# FUFO.net
KiCad netlist of a schematic drawn in Altium Designer
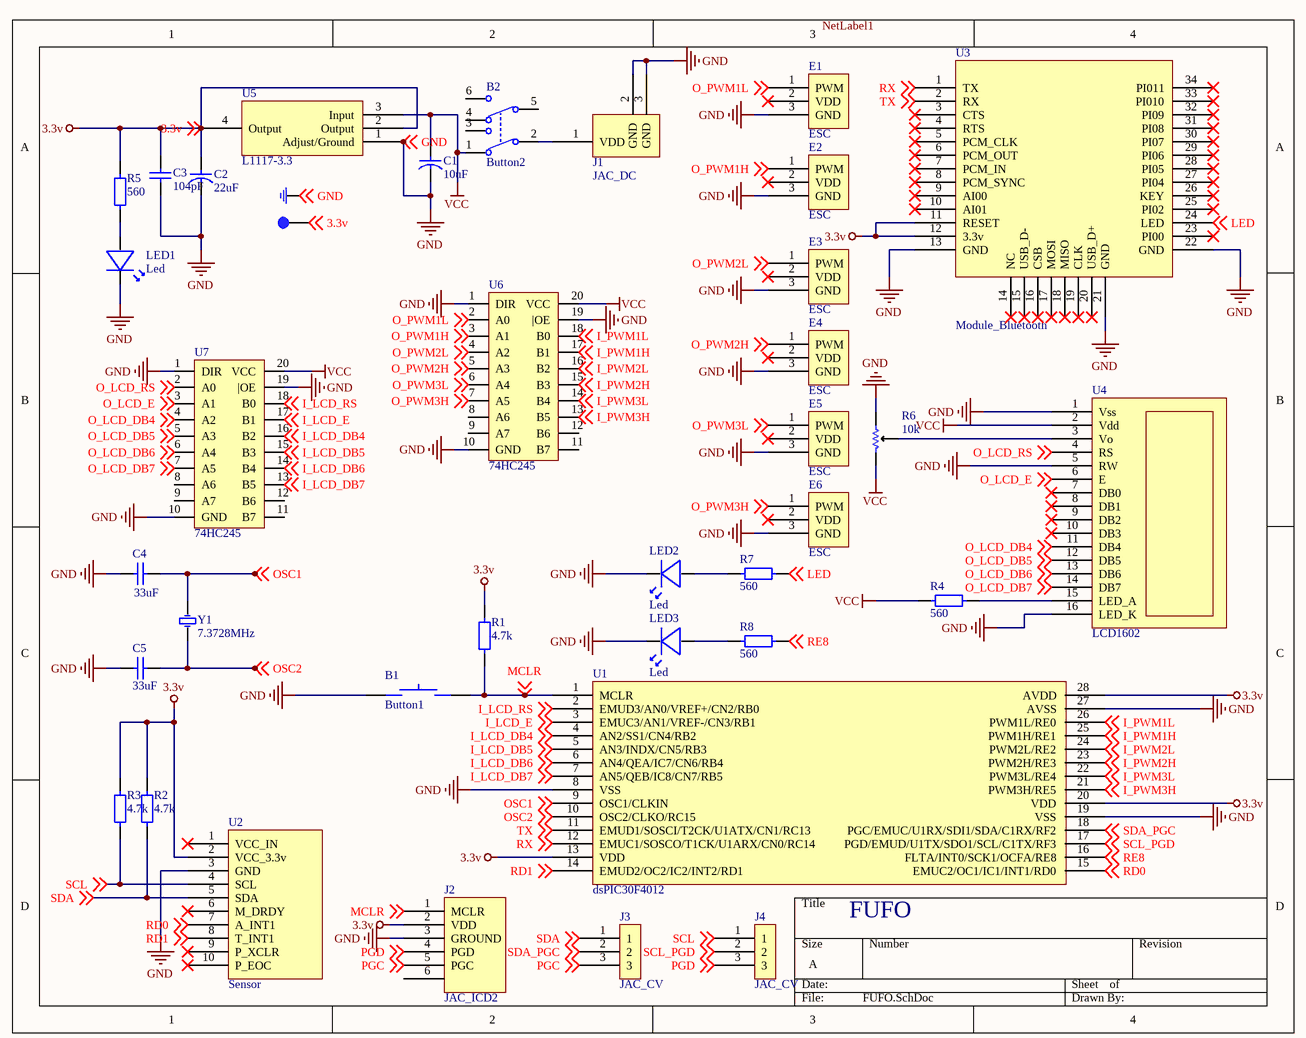
[diagram p0: FUFO.SchDoc]

(export (version "E")
  (design (tool "Eeschema 10.0.6"))
  (components
    (comp (ref "3.3v") (value "3.3v") (footprint "3.3v") (libsource (lib "FUFO") (part "3.3v")))
    (comp (ref "B1") (value "Button1") (footprint "Button1") (libsource (lib "FUFO") (part "Button1")))
    (comp (ref "B2") (value "Button2") (footprint "Button2") (libsource (lib "FUFO") (part "Button2")))
    (comp (ref "C1")
      (value "10uF")
      (footprint "Capacitor2")
      (description "Capacitor2")
      (libsource (lib "FUFO") (part "Capacitor2"))
    )
    (comp (ref "C2")
      (value "22uF")
      (footprint "Capacitor3")
      (description "Capacitor3")
      (libsource (lib "FUFO") (part "Capacitor3"))
    )
    (comp (ref "C3")
      (value "104pF")
      (footprint "Capacitor1")
      (description "Capacitor1")
      (libsource (lib "FUFO") (part "Capacitor1"))
    )
    (comp (ref "C4")
      (value "33uF")
      (footprint "Capacitor1")
      (description "Capacitor1")
      (libsource (lib "FUFO") (part "Capacitor1"))
    )
    (comp (ref "C5")
      (value "33uF")
      (footprint "Capacitor1")
      (description "Capacitor1")
      (libsource (lib "FUFO") (part "Capacitor1"))
    )
    (comp (ref "E1") (value "ESC") (footprint "ESC") (libsource (lib "FUFO") (part "ESC")))
    (comp (ref "E2") (value "ESC") (footprint "ESC") (libsource (lib "FUFO") (part "ESC")))
    (comp (ref "E3") (value "ESC") (footprint "ESC") (libsource (lib "FUFO") (part "ESC")))
    (comp (ref "E4") (value "ESC") (footprint "ESC") (libsource (lib "FUFO") (part "ESC")))
    (comp (ref "E5") (value "ESC") (footprint "ESC") (libsource (lib "FUFO") (part "ESC")))
    (comp (ref "E6") (value "ESC") (footprint "ESC") (libsource (lib "FUFO") (part "ESC")))
    (comp (ref "GND") (value "GND") (footprint "GND") (libsource (lib "FUFO") (part "GND")))
    (comp (ref "J1") (value "JAC_DC") (footprint "Jac_DC") (libsource (lib "FUFO") (part "JAC_DC")))
    (comp (ref "J2") (value "JAC_ICD2") (footprint "JAC_ICD2") (libsource (lib "FUFO") (part "JAC_ICD2")))
    (comp (ref "J3") (value "JAC_CV") (footprint "JAC_CV") (libsource (lib "FUFO") (part "JAC_CV")))
    (comp (ref "J4") (value "JAC_CV") (footprint "JAC_CV") (libsource (lib "FUFO") (part "JAC_CV")))
    (comp (ref "LED1") (value "Led") (footprint "LED") (libsource (lib "FUFO") (part "Led")))
    (comp (ref "LED2") (value "Led") (footprint "LED") (libsource (lib "FUFO") (part "Led")))
    (comp (ref "LED3") (value "Led") (footprint "LED") (libsource (lib "FUFO") (part "Led")))
    (comp (ref "R1") (value "4.7k") (footprint "Resistor") (libsource (lib "FUFO") (part "Resistor")))
    (comp (ref "R2") (value "4.7k") (footprint "Resistor") (libsource (lib "FUFO") (part "Resistor")))
    (comp (ref "R3") (value "4.7k") (footprint "Resistor") (libsource (lib "FUFO") (part "Resistor")))
    (comp (ref "R4") (value "560") (footprint "Resistor") (libsource (lib "FUFO") (part "Resistor")))
    (comp (ref "R5") (value "560") (footprint "Resistor") (libsource (lib "FUFO") (part "Resistor")))
    (comp (ref "R6") (value "10k") (footprint "BienTro") (libsource (lib "FUFO") (part "BienTro")))
    (comp (ref "R7") (value "560") (footprint "Resistor") (libsource (lib "FUFO") (part "Resistor")))
    (comp (ref "R8") (value "560") (footprint "Resistor") (libsource (lib "FUFO") (part "Resistor")))
    (comp (ref "U1")
      (value "dsPIC30F4012")
      (footprint "dsPIC30F4012")
      (libsource (lib "FUFO") (part "dsPIC30F4012"))
    )
    (comp (ref "U2") (value "Sensor") (footprint "Sensor") (libsource (lib "FUFO") (part "Sensor")))
    (comp (ref "U3")
      (value "Module_Bluetooth")
      (footprint "Module_Bluetooth")
      (libsource (lib "FUFO") (part "Module_Bluetooth"))
    )
    (comp (ref "U4") (value "LCD1602") (footprint "LCD1602") (libsource (lib "FUFO") (part "LCD1602")))
    (comp (ref "U5")
      (value "L1117-3.3")
      (footprint "L1117 - 3.3")
      (libsource (lib "FUFO") (part "L1117-3.3"))
    )
    (comp (ref "U6") (value "74HC245") (footprint "74HC245") (libsource (lib "FUFO") (part "74HC245")))
    (comp (ref "U7") (value "74HC245") (footprint "74HC245") (libsource (lib "FUFO") (part "74HC245")))
    (comp (ref "Y1") (value "7.3728MHz") (footprint "XTAL") (libsource (lib "FUFO") (part "XTAL")))
  )
  (nets
    (net (code "2") (name "3.3v") (class "Default")
      (node (ref "3.3v") (pin "0") (pinfunction "0_0") (pintype "passive"))
      (node (ref "C2") (pin "1") (pinfunction "1_1") (pintype "passive"))
      (node (ref "C3") (pin "2") (pinfunction "2_2") (pintype "passive"))
      (node (ref "J2") (pin "2") (pinfunction "VDD_2") (pintype "passive"))
      (node (ref "R1") (pin "2") (pinfunction "2_2") (pintype "passive"))
      (node (ref "R2") (pin "2") (pinfunction "2_2") (pintype "passive"))
      (node (ref "R3") (pin "2") (pinfunction "2_2") (pintype "passive"))
      (node (ref "R5") (pin "2") (pinfunction "2_2") (pintype "passive"))
      (node (ref "U1") (pin "13") (pinfunction "VDD_13") (pintype "passive"))
      (node (ref "U1") (pin "20") (pinfunction "VDD_20") (pintype "passive"))
      (node (ref "U1") (pin "28") (pinfunction "AVDD_28") (pintype "passive"))
      (node (ref "U2") (pin "2") (pinfunction "VCC_3.3v_2") (pintype "passive"))
      (node (ref "U3") (pin "11") (pinfunction "RESET_11") (pintype "passive"))
      (node (ref "U3") (pin "12") (pinfunction "3.3v_12") (pintype "passive"))
      (node (ref "U5") (pin "2") (pinfunction "Output_2") (pintype "passive"))
      (node (ref "U5") (pin "4") (pinfunction "Output_4") (pintype "passive"))
    )
    (net (code "3") (name "GND") (class "Default")
      (node (ref "B1") (pin "1") (pinfunction "1_1") (pintype "passive"))
      (node (ref "C1") (pin "2") (pinfunction "2_2") (pintype "passive"))
      (node (ref "C2") (pin "2") (pinfunction "2_2") (pintype "passive"))
      (node (ref "C3") (pin "1") (pinfunction "1_1") (pintype "passive"))
      (node (ref "C4") (pin "1") (pinfunction "1_1") (pintype "passive"))
      (node (ref "C5") (pin "1") (pinfunction "1_1") (pintype "passive"))
      (node (ref "E1") (pin "3") (pinfunction "GND_3") (pintype "passive"))
      (node (ref "E2") (pin "3") (pinfunction "GND_3") (pintype "passive"))
      (node (ref "E3") (pin "3") (pinfunction "GND_3") (pintype "passive"))
      (node (ref "E4") (pin "3") (pinfunction "GND_3") (pintype "passive"))
      (node (ref "E5") (pin "3") (pinfunction "GND_3") (pintype "passive"))
      (node (ref "E6") (pin "3") (pinfunction "GND_3") (pintype "passive"))
      (node (ref "GND") (pin "0") (pinfunction "0_0") (pintype "passive"))
      (node (ref "J1") (pin "2") (pinfunction "GND_2") (pintype "passive"))
      (node (ref "J1") (pin "3") (pinfunction "GND_3") (pintype "passive"))
      (node (ref "J2") (pin "3") (pinfunction "GROUND_3") (pintype "passive"))
      (node (ref "LED1") (pin "2") (pinfunction "2_2") (pintype "passive"))
      (node (ref "LED2") (pin "2") (pinfunction "2_2") (pintype "passive"))
      (node (ref "LED3") (pin "2") (pinfunction "2_2") (pintype "passive"))
      (node (ref "R6") (pin "0") (pinfunction "0_0") (pintype "passive"))
      (node (ref "U1") (pin "19") (pinfunction "VSS_19") (pintype "passive"))
      (node (ref "U1") (pin "27") (pinfunction "AVSS_27") (pintype "passive"))
      (node (ref "U1") (pin "8") (pinfunction "VSS_8") (pintype "passive"))
      (node (ref "U2") (pin "3") (pinfunction "GND_3") (pintype "passive"))
      (node (ref "U3") (pin "13") (pinfunction "GND_13") (pintype "passive"))
      (node (ref "U3") (pin "21") (pinfunction "GND_21") (pintype "passive"))
      (node (ref "U3") (pin "22") (pinfunction "GND_22") (pintype "passive"))
      (node (ref "U4") (pin "1") (pinfunction "Vss_1") (pintype "passive"))
      (node (ref "U4") (pin "16") (pinfunction "LED_K_16") (pintype "passive"))
      (node (ref "U4") (pin "5") (pinfunction "RW_5") (pintype "passive"))
      (node (ref "U5") (pin "1") (pinfunction "Adjust/Ground_1") (pintype "passive"))
      (node (ref "U6") (pin "1") (pinfunction "DIR_1") (pintype "passive"))
      (node (ref "U6") (pin "10") (pinfunction "GND_10") (pintype "passive"))
      (node (ref "U6") (pin "19") (pinfunction "OE_19") (pintype "passive"))
      (node (ref "U7") (pin "1") (pinfunction "DIR_1") (pintype "passive"))
      (node (ref "U7") (pin "10") (pinfunction "GND_10") (pintype "passive"))
      (node (ref "U7") (pin "19") (pinfunction "OE_19") (pintype "passive"))
    )
    (net (code "4") (name "I_LCD_DB4") (class "Default")
      (node (ref "U1") (pin "4") (pinfunction "AN2/SS1/CN4/RB2_4") (pintype "passive"))
      (node (ref "U7") (pin "16") (pinfunction "B2_16") (pintype "passive"))
    )
    (net (code "5") (name "I_LCD_DB5") (class "Default")
      (node (ref "U1") (pin "5") (pinfunction "AN3/INDX/CN5/RB3_5") (pintype "passive"))
      (node (ref "U7") (pin "15") (pinfunction "B3_15") (pintype "passive"))
    )
    (net (code "6") (name "I_LCD_DB6") (class "Default")
      (node (ref "U1") (pin "6") (pinfunction "AN4/QEA/IC7/CN6/RB4_6") (pintype "passive"))
      (node (ref "U7") (pin "14") (pinfunction "B4_14") (pintype "passive"))
    )
    (net (code "7") (name "I_LCD_DB7") (class "Default")
      (node (ref "U1") (pin "7") (pinfunction "AN5/QEB/IC8/CN7/RB5_7") (pintype "passive"))
      (node (ref "U7") (pin "13") (pinfunction "B5_13") (pintype "passive"))
    )
    (net (code "8") (name "I_LCD_E") (class "Default")
      (node (ref "U1") (pin "3") (pinfunction "EMUC3/AN1/VREF-/CN3/RB1_3") (pintype "passive"))
      (node (ref "U7") (pin "17") (pinfunction "B1_17") (pintype "passive"))
    )
    (net (code "9") (name "I_LCD_RS") (class "Default")
      (node (ref "U1") (pin "2") (pinfunction "EMUD3/AN0/VREF+/CN2/RB0_2") (pintype "passive"))
      (node (ref "U7") (pin "18") (pinfunction "B0_18") (pintype "passive"))
    )
    (net (code "10") (name "I_PWM1H") (class "Default")
      (node (ref "U1") (pin "25") (pinfunction "PWM1H/RE1_25") (pintype "passive"))
      (node (ref "U6") (pin "17") (pinfunction "B1_17") (pintype "passive"))
    )
    (net (code "11") (name "I_PWM1L") (class "Default")
      (node (ref "U1") (pin "26") (pinfunction "PWM1L/RE0_26") (pintype "passive"))
      (node (ref "U6") (pin "18") (pinfunction "B0_18") (pintype "passive"))
    )
    (net (code "12") (name "I_PWM2H") (class "Default")
      (node (ref "U1") (pin "23") (pinfunction "PWM2H/RE3_23") (pintype "passive"))
      (node (ref "U6") (pin "15") (pinfunction "B3_15") (pintype "passive"))
    )
    (net (code "13") (name "I_PWM2L") (class "Default")
      (node (ref "U1") (pin "24") (pinfunction "PWM2L/RE2_24") (pintype "passive"))
      (node (ref "U6") (pin "16") (pinfunction "B2_16") (pintype "passive"))
    )
    (net (code "14") (name "I_PWM3H") (class "Default")
      (node (ref "U1") (pin "21") (pinfunction "PWM3H/RE5_21") (pintype "passive"))
      (node (ref "U6") (pin "13") (pinfunction "B5_13") (pintype "passive"))
    )
    (net (code "15") (name "I_PWM3L") (class "Default")
      (node (ref "U1") (pin "22") (pinfunction "PWM3L/RE4_22") (pintype "passive"))
      (node (ref "U6") (pin "14") (pinfunction "B4_14") (pintype "passive"))
    )
    (net (code "16") (name "LED") (class "Default")
      (node (ref "R7") (pin "2") (pinfunction "2_2") (pintype "passive"))
      (node (ref "U3") (pin "24") (pinfunction "LED_24") (pintype "passive"))
    )
    (net (code "17") (name "MCLR") (class "Default")
      (node (ref "B1") (pin "2") (pinfunction "2_2") (pintype "passive"))
      (node (ref "J2") (pin "1") (pinfunction "MCLR_1") (pintype "passive"))
      (node (ref "R1") (pin "1") (pinfunction "1_1") (pintype "passive"))
      (node (ref "U1") (pin "1") (pinfunction "MCLR_1") (pintype "passive"))
    )
    (net (code "18") (name "Net-(B2-1)") (class "Default")
      (node (ref "B2") (pin "2") (pinfunction "1_2") (pintype "passive"))
      (node (ref "J1") (pin "1") (pinfunction "VDD_1") (pintype "passive"))
    )
    (net (code "19") (name "Net-(LED1-Pad1)") (class "Default")
      (node (ref "LED1") (pin "1") (pinfunction "1_1") (pintype "passive"))
      (node (ref "R5") (pin "1") (pinfunction "1_1") (pintype "passive"))
    )
    (net (code "20") (name "Net-(LED2-Pad1)") (class "Default")
      (node (ref "LED2") (pin "1") (pinfunction "1_1") (pintype "passive"))
      (node (ref "R7") (pin "1") (pinfunction "1_1") (pintype "passive"))
    )
    (net (code "21") (name "Net-(LED3-Pad1)") (class "Default")
      (node (ref "LED3") (pin "1") (pinfunction "1_1") (pintype "passive"))
      (node (ref "R8") (pin "1") (pinfunction "1_1") (pintype "passive"))
    )
    (net (code "22") (name "Net-(U4-LED_A)") (class "Default")
      (node (ref "R4") (pin "2") (pinfunction "2_2") (pintype "passive"))
      (node (ref "U4") (pin "15") (pinfunction "LED_A_15") (pintype "passive"))
    )
    (net (code "23") (name "Net-(U4-Vo)") (class "Default")
      (node (ref "R6") (pin "1") (pinfunction "1_1") (pintype "passive"))
      (node (ref "U4") (pin "3") (pinfunction "Vo_3") (pintype "passive"))
    )
    (net (code "24") (name "OSC1") (class "Default")
      (node (ref "C4") (pin "2") (pinfunction "2_2") (pintype "passive"))
      (node (ref "U1") (pin "9") (pinfunction "OSC1/CLKIN_9") (pintype "passive"))
      (node (ref "Y1") (pin "2") (pinfunction "2_2") (pintype "passive"))
    )
    (net (code "25") (name "OSC2") (class "Default")
      (node (ref "C5") (pin "2") (pinfunction "2_2") (pintype "passive"))
      (node (ref "U1") (pin "10") (pinfunction "OSC2/CLKO/RC15_10") (pintype "passive"))
      (node (ref "Y1") (pin "1") (pinfunction "1_1") (pintype "passive"))
    )
    (net (code "26") (name "O_LCD_DB4") (class "Default")
      (node (ref "U4") (pin "11") (pinfunction "DB4_11") (pintype "passive"))
      (node (ref "U7") (pin "4") (pinfunction "A2_4") (pintype "passive"))
    )
    (net (code "27") (name "O_LCD_DB5") (class "Default")
      (node (ref "U4") (pin "12") (pinfunction "DB5_12") (pintype "passive"))
      (node (ref "U7") (pin "5") (pinfunction "A3_5") (pintype "passive"))
    )
    (net (code "28") (name "O_LCD_DB6") (class "Default")
      (node (ref "U4") (pin "13") (pinfunction "DB6_13") (pintype "passive"))
      (node (ref "U7") (pin "6") (pinfunction "A4_6") (pintype "passive"))
    )
    (net (code "29") (name "O_LCD_DB7") (class "Default")
      (node (ref "U4") (pin "14") (pinfunction "DB7_14") (pintype "passive"))
      (node (ref "U7") (pin "7") (pinfunction "A5_7") (pintype "passive"))
    )
    (net (code "30") (name "O_LCD_E") (class "Default")
      (node (ref "U4") (pin "6") (pinfunction "E_6") (pintype "passive"))
      (node (ref "U7") (pin "3") (pinfunction "A1_3") (pintype "passive"))
    )
    (net (code "31") (name "O_LCD_RS") (class "Default")
      (node (ref "U4") (pin "4") (pinfunction "RS_4") (pintype "passive"))
      (node (ref "U7") (pin "2") (pinfunction "A0_2") (pintype "passive"))
    )
    (net (code "32") (name "O_PWM1H") (class "Default")
      (node (ref "E2") (pin "1") (pinfunction "PWM_1") (pintype "passive"))
      (node (ref "U6") (pin "3") (pinfunction "A1_3") (pintype "passive"))
    )
    (net (code "33") (name "O_PWM1L") (class "Default")
      (node (ref "E1") (pin "1") (pinfunction "PWM_1") (pintype "passive"))
      (node (ref "U6") (pin "2") (pinfunction "A0_2") (pintype "passive"))
    )
    (net (code "34") (name "O_PWM2H") (class "Default")
      (node (ref "E4") (pin "1") (pinfunction "PWM_1") (pintype "passive"))
      (node (ref "U6") (pin "5") (pinfunction "A3_5") (pintype "passive"))
    )
    (net (code "35") (name "O_PWM2L") (class "Default")
      (node (ref "E3") (pin "1") (pinfunction "PWM_1") (pintype "passive"))
      (node (ref "U6") (pin "4") (pinfunction "A2_4") (pintype "passive"))
    )
    (net (code "36") (name "O_PWM3H") (class "Default")
      (node (ref "E6") (pin "1") (pinfunction "PWM_1") (pintype "passive"))
      (node (ref "U6") (pin "7") (pinfunction "A5_7") (pintype "passive"))
    )
    (net (code "37") (name "O_PWM3L") (class "Default")
      (node (ref "E5") (pin "1") (pinfunction "PWM_1") (pintype "passive"))
      (node (ref "U6") (pin "6") (pinfunction "A4_6") (pintype "passive"))
    )
    (net (code "38") (name "PGC") (class "Default")
      (node (ref "J2") (pin "5") (pinfunction "PGC_5") (pintype "passive"))
      (node (ref "J3") (pin "3") (pinfunction "3_3") (pintype "passive"))
    )
    (net (code "39") (name "PGD") (class "Default")
      (node (ref "J2") (pin "4") (pinfunction "PGD_4") (pintype "passive"))
      (node (ref "J4") (pin "3") (pinfunction "3_3") (pintype "passive"))
    )
    (net (code "40") (name "RD0") (class "Default")
      (node (ref "U1") (pin "15") (pinfunction "EMUC2/OC1/IC1/INT1/RD0_15") (pintype "passive"))
      (node (ref "U2") (pin "7") (pinfunction "A_INT1_7") (pintype "passive"))
    )
    (net (code "41") (name "RD1") (class "Default")
      (node (ref "U1") (pin "14") (pinfunction "EMUD2/OC2/IC2/INT2/RD1_14") (pintype "passive"))
      (node (ref "U2") (pin "8") (pinfunction "T_INT1_8") (pintype "passive"))
    )
    (net (code "42") (name "RE8") (class "Default")
      (node (ref "R8") (pin "2") (pinfunction "2_2") (pintype "passive"))
      (node (ref "U1") (pin "16") (pinfunction "FLTA/INT0/SCK1/OCFA/RE8_16") (pintype "passive"))
    )
    (net (code "43") (name "RX") (class "Default")
      (node (ref "U1") (pin "12") (pinfunction "EMUC1/SOSCO/T1CK/U1ARX/CN0/RC14_12") (pintype "passive"))
      (node (ref "U3") (pin "1") (pinfunction "TX_1") (pintype "passive"))
    )
    (net (code "44") (name "SCL") (class "Default")
      (node (ref "J4") (pin "1") (pinfunction "1_1") (pintype "passive"))
      (node (ref "R3") (pin "1") (pinfunction "1_1") (pintype "passive"))
      (node (ref "U2") (pin "4") (pinfunction "SCL_4") (pintype "passive"))
    )
    (net (code "45") (name "SCL_PGD") (class "Default")
      (node (ref "J4") (pin "2") (pinfunction "2_2") (pintype "passive"))
      (node (ref "U1") (pin "17") (pinfunction "PGD/EMUD/U1TX/SDO1/SCL/C1TX/RF3_17") (pintype "passive"))
    )
    (net (code "46") (name "SDA") (class "Default")
      (node (ref "J3") (pin "1") (pinfunction "1_1") (pintype "passive"))
      (node (ref "R2") (pin "1") (pinfunction "1_1") (pintype "passive"))
      (node (ref "U2") (pin "5") (pinfunction "SDA_5") (pintype "passive"))
    )
    (net (code "47") (name "SDA_PGC") (class "Default")
      (node (ref "J3") (pin "2") (pinfunction "2_2") (pintype "passive"))
      (node (ref "U1") (pin "18") (pinfunction "PGC/EMUC/U1RX/SDI1/SDA/C1RX/RF2_18") (pintype "passive"))
    )
    (net (code "48") (name "TX") (class "Default")
      (node (ref "U1") (pin "11") (pinfunction "EMUD1/SOSCI/T2CK/U1ATX/CN1/RC13_11") (pintype "passive"))
      (node (ref "U3") (pin "2") (pinfunction "RX_2") (pintype "passive"))
    )
    (net (code "49") (name "VCC") (class "Default")
      (node (ref "B2") (pin "1") (pinfunction "4_1") (pintype "passive"))
      (node (ref "C1") (pin "1") (pinfunction "1_1") (pintype "passive"))
      (node (ref "R4") (pin "1") (pinfunction "1_1") (pintype "passive"))
      (node (ref "R6") (pin "2") (pinfunction "2_2") (pintype "passive"))
      (node (ref "U4") (pin "2") (pinfunction "Vdd_2") (pintype "passive"))
      (node (ref "U5") (pin "3") (pinfunction "Input_3") (pintype "passive"))
      (node (ref "U6") (pin "20") (pinfunction "VCC_20") (pintype "passive"))
      (node (ref "U7") (pin "20") (pinfunction "VCC_20") (pintype "passive"))
    )
    (net (code "50") (name "unconnected-(B2-5-Pad3)") (class "Default")
      (node (ref "B2") (pin "3") (pinfunction "5_3") (pintype "passive"))
    )
    (net (code "51") (name "unconnected-(B2-Pad4)") (class "Default")
      (node (ref "B2") (pin "4") (pinfunction "4_4") (pintype "passive"))
    )
    (net (code "52") (name "unconnected-(B2-Pad5)") (class "Default")
      (node (ref "B2") (pin "5") (pinfunction "5_5") (pintype "passive"))
    )
    (net (code "53") (name "unconnected-(B2-Pad6)") (class "Default")
      (node (ref "B2") (pin "6") (pinfunction "6_6") (pintype "passive"))
    )
    (net (code "54") (name "unconnected-(E1-VDD-Pad2)") (class "Default")
      (node (ref "E1") (pin "2") (pinfunction "VDD_2") (pintype "passive+no_connect"))
    )
    (net (code "55") (name "unconnected-(E2-VDD-Pad2)") (class "Default")
      (node (ref "E2") (pin "2") (pinfunction "VDD_2") (pintype "passive+no_connect"))
    )
    (net (code "56") (name "unconnected-(E3-VDD-Pad2)") (class "Default")
      (node (ref "E3") (pin "2") (pinfunction "VDD_2") (pintype "passive+no_connect"))
    )
    (net (code "57") (name "unconnected-(E4-VDD-Pad2)") (class "Default")
      (node (ref "E4") (pin "2") (pinfunction "VDD_2") (pintype "passive+no_connect"))
    )
    (net (code "58") (name "unconnected-(E5-VDD-Pad2)") (class "Default")
      (node (ref "E5") (pin "2") (pinfunction "VDD_2") (pintype "passive+no_connect"))
    )
    (net (code "59") (name "unconnected-(E6-VDD-Pad2)") (class "Default")
      (node (ref "E6") (pin "2") (pinfunction "VDD_2") (pintype "passive+no_connect"))
    )
    (net (code "60") (name "unconnected-(J2-Pad6)") (class "Default")
      (node (ref "J2") (pin "6") (pinfunction "6_6") (pintype "passive"))
    )
    (net (code "61") (name "unconnected-(U2-M_DRDY-Pad6)") (class "Default")
      (node (ref "U2") (pin "6") (pinfunction "M_DRDY_6") (pintype "passive+no_connect"))
    )
    (net (code "62") (name "unconnected-(U2-P_EOC-Pad10)") (class "Default")
      (node (ref "U2") (pin "10") (pinfunction "P_EOC_10") (pintype "passive+no_connect"))
    )
    (net (code "63") (name "unconnected-(U2-P_XCLR-Pad9)") (class "Default")
      (node (ref "U2") (pin "9") (pinfunction "P_XCLR_9") (pintype "passive+no_connect"))
    )
    (net (code "64") (name "unconnected-(U2-VCC_IN-Pad1)") (class "Default")
      (node (ref "U2") (pin "1") (pinfunction "VCC_IN_1") (pintype "passive+no_connect"))
    )
    (net (code "65") (name "unconnected-(U3-AI00-Pad9)") (class "Default")
      (node (ref "U3") (pin "9") (pinfunction "AI00_9") (pintype "passive+no_connect"))
    )
    (net (code "66") (name "unconnected-(U3-AI01-Pad10)") (class "Default")
      (node (ref "U3") (pin "10") (pinfunction "AI01_10") (pintype "passive+no_connect"))
    )
    (net (code "67") (name "unconnected-(U3-CLK-Pad19)") (class "Default")
      (node (ref "U3") (pin "19") (pinfunction "CLK_19") (pintype "passive+no_connect"))
    )
    (net (code "68") (name "unconnected-(U3-CSB-Pad16)") (class "Default")
      (node (ref "U3") (pin "16") (pinfunction "CSB_16") (pintype "passive+no_connect"))
    )
    (net (code "69") (name "unconnected-(U3-CTS-Pad3)") (class "Default")
      (node (ref "U3") (pin "3") (pinfunction "CTS_3") (pintype "passive+no_connect"))
    )
    (net (code "70") (name "unconnected-(U3-KEY-Pad26)") (class "Default")
      (node (ref "U3") (pin "26") (pinfunction "KEY_26") (pintype "passive+no_connect"))
    )
    (net (code "71") (name "unconnected-(U3-MISO-Pad18)") (class "Default")
      (node (ref "U3") (pin "18") (pinfunction "MISO_18") (pintype "passive+no_connect"))
    )
    (net (code "72") (name "unconnected-(U3-MOSI-Pad17)") (class "Default")
      (node (ref "U3") (pin "17") (pinfunction "MOSI_17") (pintype "passive+no_connect"))
    )
    (net (code "73") (name "unconnected-(U3-NC-Pad14)") (class "Default")
      (node (ref "U3") (pin "14") (pinfunction "NC_14") (pintype "passive+no_connect"))
    )
    (net (code "74") (name "unconnected-(U3-PCM_CLK-Pad5)") (class "Default")
      (node (ref "U3") (pin "5") (pinfunction "PCM_CLK_5") (pintype "passive+no_connect"))
    )
    (net (code "75") (name "unconnected-(U3-PCM_IN-Pad7)") (class "Default")
      (node (ref "U3") (pin "7") (pinfunction "PCM_IN_7") (pintype "passive+no_connect"))
    )
    (net (code "76") (name "unconnected-(U3-PCM_OUT-Pad6)") (class "Default")
      (node (ref "U3") (pin "6") (pinfunction "PCM_OUT_6") (pintype "passive+no_connect"))
    )
    (net (code "77") (name "unconnected-(U3-PCM_SYNC-Pad8)") (class "Default")
      (node (ref "U3") (pin "8") (pinfunction "PCM_SYNC_8") (pintype "passive+no_connect"))
    )
    (net (code "78") (name "unconnected-(U3-PI00-Pad23)") (class "Default")
      (node (ref "U3") (pin "23") (pinfunction "PI00_23") (pintype "passive+no_connect"))
    )
    (net (code "79") (name "unconnected-(U3-PI02-Pad25)") (class "Default")
      (node (ref "U3") (pin "25") (pinfunction "PI02_25") (pintype "passive+no_connect"))
    )
    (net (code "80") (name "unconnected-(U3-PI04-Pad27)") (class "Default")
      (node (ref "U3") (pin "27") (pinfunction "PI04_27") (pintype "passive+no_connect"))
    )
    (net (code "81") (name "unconnected-(U3-PI05-Pad28)") (class "Default")
      (node (ref "U3") (pin "28") (pinfunction "PI05_28") (pintype "passive+no_connect"))
    )
    (net (code "82") (name "unconnected-(U3-PI06-Pad29)") (class "Default")
      (node (ref "U3") (pin "29") (pinfunction "PI06_29") (pintype "passive+no_connect"))
    )
    (net (code "83") (name "unconnected-(U3-PI07-Pad30)") (class "Default")
      (node (ref "U3") (pin "30") (pinfunction "PI07_30") (pintype "passive+no_connect"))
    )
    (net (code "84") (name "unconnected-(U3-PI08-Pad31)") (class "Default")
      (node (ref "U3") (pin "31") (pinfunction "PI08_31") (pintype "passive+no_connect"))
    )
    (net (code "85") (name "unconnected-(U3-PI09-Pad32)") (class "Default")
      (node (ref "U3") (pin "32") (pinfunction "PI09_32") (pintype "passive+no_connect"))
    )
    (net (code "86") (name "unconnected-(U3-PI010-Pad33)") (class "Default")
      (node (ref "U3") (pin "33") (pinfunction "PI010_33") (pintype "passive+no_connect"))
    )
    (net (code "87") (name "unconnected-(U3-PI011-Pad34)") (class "Default")
      (node (ref "U3") (pin "34") (pinfunction "PI011_34") (pintype "passive+no_connect"))
    )
    (net (code "88") (name "unconnected-(U3-RTS-Pad4)") (class "Default")
      (node (ref "U3") (pin "4") (pinfunction "RTS_4") (pintype "passive+no_connect"))
    )
    (net (code "89") (name "unconnected-(U3-USB_D+-Pad20)") (class "Default")
      (node (ref "U3") (pin "20") (pinfunction "USB_D+_20") (pintype "passive+no_connect"))
    )
    (net (code "90") (name "unconnected-(U3-USB_D--Pad15)") (class "Default")
      (node (ref "U3") (pin "15") (pinfunction "USB_D-_15") (pintype "passive+no_connect"))
    )
    (net (code "91") (name "unconnected-(U4-DB0-Pad7)") (class "Default")
      (node (ref "U4") (pin "7") (pinfunction "DB0_7") (pintype "passive+no_connect"))
    )
    (net (code "92") (name "unconnected-(U4-DB1-Pad8)") (class "Default")
      (node (ref "U4") (pin "8") (pinfunction "DB1_8") (pintype "passive+no_connect"))
    )
    (net (code "93") (name "unconnected-(U4-DB2-Pad9)") (class "Default")
      (node (ref "U4") (pin "9") (pinfunction "DB2_9") (pintype "passive+no_connect"))
    )
    (net (code "94") (name "unconnected-(U4-DB3-Pad10)") (class "Default")
      (node (ref "U4") (pin "10") (pinfunction "DB3_10") (pintype "passive+no_connect"))
    )
    (net (code "95") (name "unconnected-(U6-A6-Pad8)") (class "Default")
      (node (ref "U6") (pin "8") (pinfunction "A6_8") (pintype "passive"))
    )
    (net (code "96") (name "unconnected-(U6-A7-Pad9)") (class "Default")
      (node (ref "U6") (pin "9") (pinfunction "A7_9") (pintype "passive"))
    )
    (net (code "97") (name "unconnected-(U6-B6-Pad12)") (class "Default")
      (node (ref "U6") (pin "12") (pinfunction "B6_12") (pintype "passive"))
    )
    (net (code "98") (name "unconnected-(U6-B7-Pad11)") (class "Default")
      (node (ref "U6") (pin "11") (pinfunction "B7_11") (pintype "passive"))
    )
    (net (code "99") (name "unconnected-(U7-A6-Pad8)") (class "Default")
      (node (ref "U7") (pin "8") (pinfunction "A6_8") (pintype "passive"))
    )
    (net (code "100") (name "unconnected-(U7-A7-Pad9)") (class "Default")
      (node (ref "U7") (pin "9") (pinfunction "A7_9") (pintype "passive"))
    )
    (net (code "101") (name "unconnected-(U7-B6-Pad12)") (class "Default")
      (node (ref "U7") (pin "12") (pinfunction "B6_12") (pintype "passive"))
    )
    (net (code "102") (name "unconnected-(U7-B7-Pad11)") (class "Default")
      (node (ref "U7") (pin "11") (pinfunction "B7_11") (pintype "passive"))
    )
  )
)
